# v0_3_2.net
KiCad netlist of a schematic drawn in EAGLE
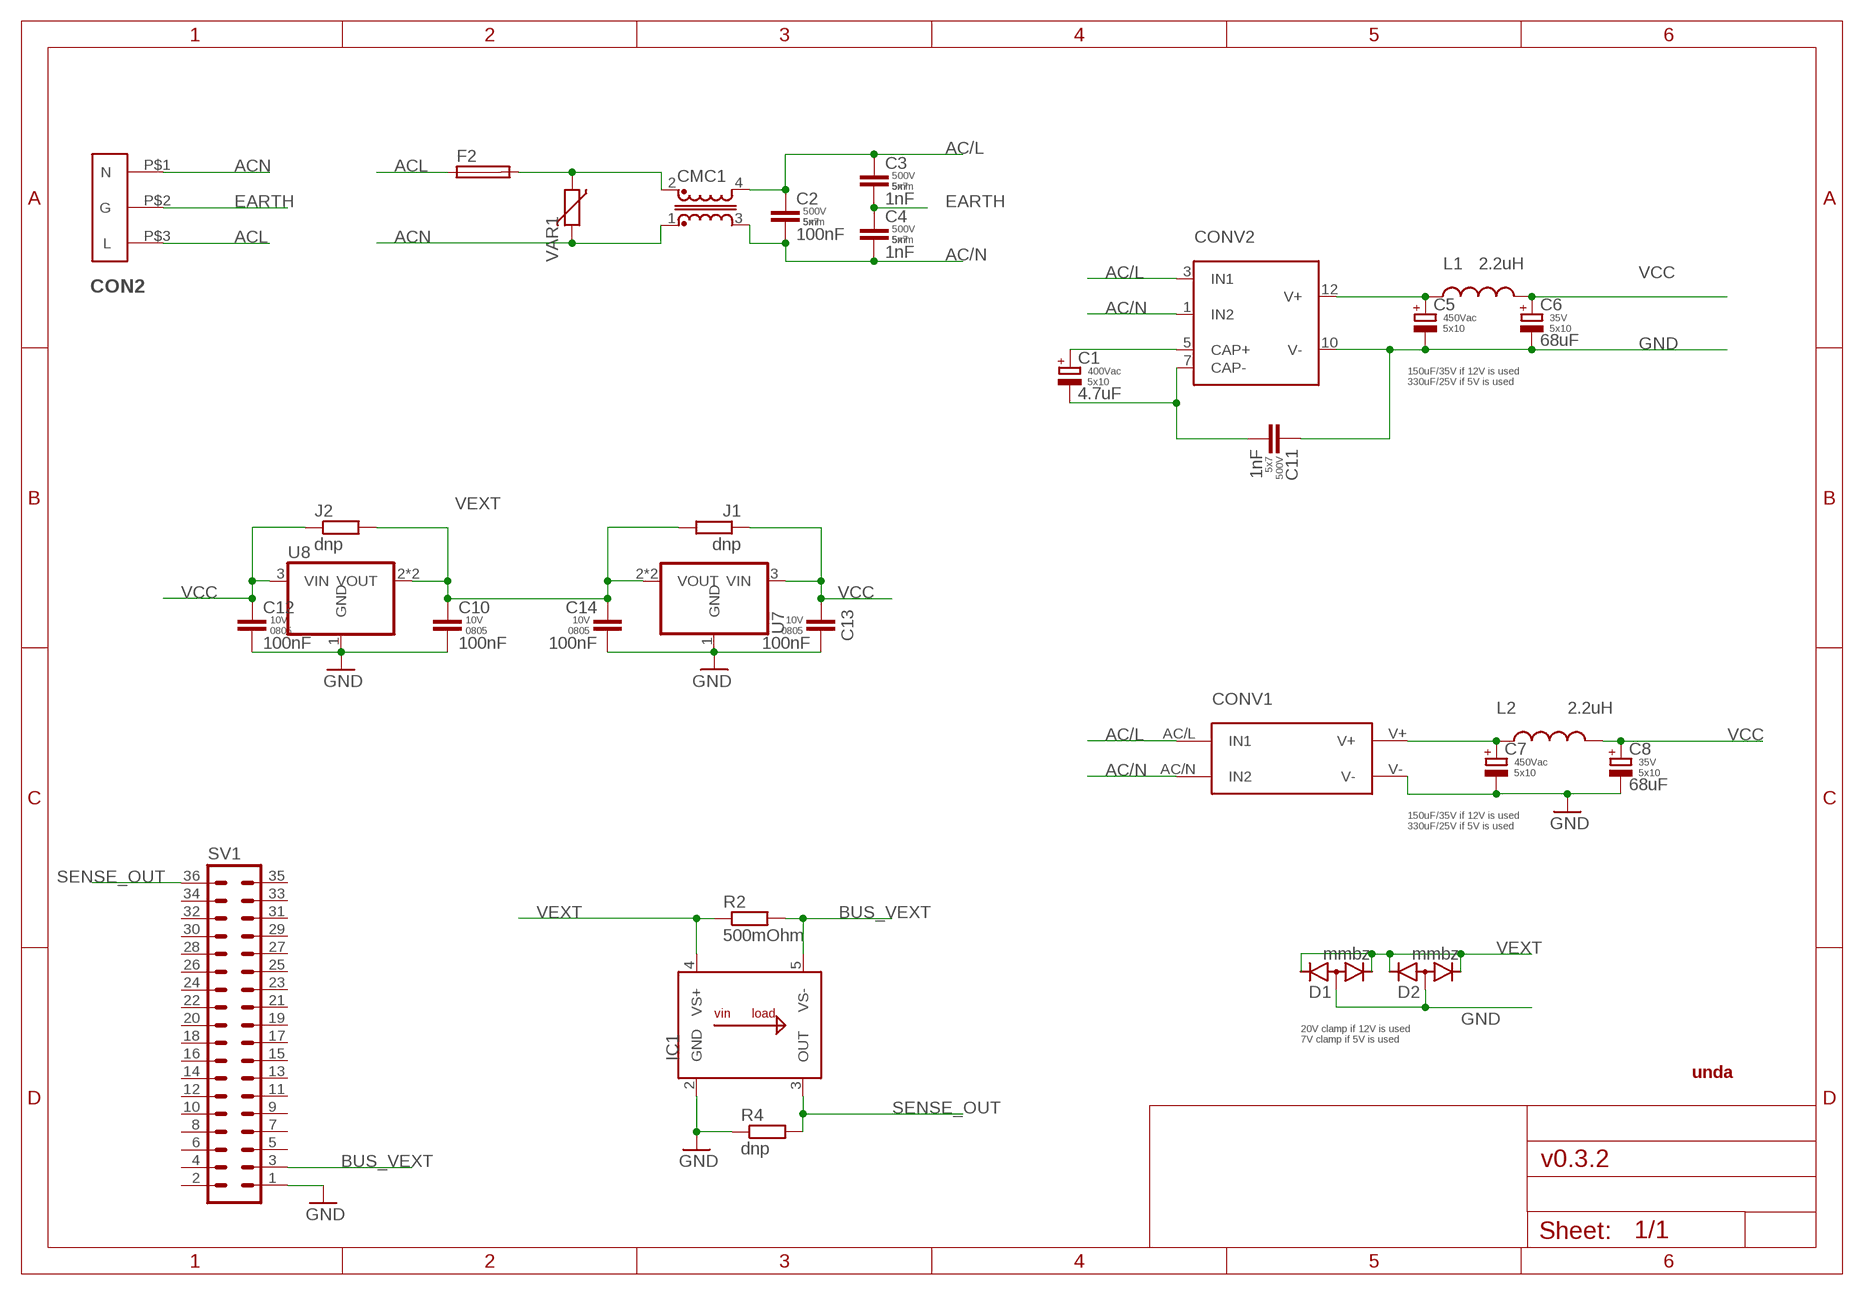
[diagram p0: schematic, sheet 1]

(export (version "E")
  (design (tool "Eeschema 10.0.6"))
  (components
    (comp (ref "C1")
      (value "4.7uF")
      (footprint "eagle-import:CAPPRD508W65D1000H1600B")
      (fields
        (field (name "PACKAGE") "5x10")
        (field (name "RATING") "450Vac")
        (field (name "RATING_1") "400Vac")
      )
      (libsource (lib "eagle-import") (part "CAP-POL-5PX10WX16H"))
    )
    (comp (ref "C2")
      (value "100nF")
      (footprint "eagle-import:C050-025X075")
      (fields
        (field (name "RATING") "500V")
        (field (name "DIMENSIONS") "5mm")
        (field (name "RATING_1") "500V")
      )
      (libsource (lib "eagle-import") (part "CAP-P5W6H8T2.5"))
    )
    (comp (ref "C3")
      (value "1nF")
      (footprint "eagle-import:C050-025X075")
      (fields
        (field (name "RATING") "500V")
        (field (name "DIMENSIONS") "5mm")
        (field (name "RATING_1") "500V")
      )
      (libsource (lib "eagle-import") (part "CAP-P5W6H8T2.5"))
    )
    (comp (ref "C4")
      (value "1nF")
      (footprint "eagle-import:C050-025X075")
      (fields
        (field (name "RATING") "500V")
        (field (name "DIMENSIONS") "5mm")
        (field (name "RATING_1") "500V")
      )
      (libsource (lib "eagle-import") (part "CAP-P5W6H8T2.5"))
    )
    (comp (ref "C5")
      (value "CAP-POL-5PX10WX16H")
      (footprint "eagle-import:CAPPRD508W65D1000H1600B")
      (libsource (lib "eagle-import") (part "CAP-POL-5PX10WX16H"))
    )
    (comp (ref "C6")
      (value "68uF")
      (footprint "eagle-import:CAPPRD508W65D1000H1600B")
      (fields
        (field (name "PACKAGE") "5x10")
        (field (name "RATING") "450Vac")
        (field (name "RATING_1") "35V")
      )
      (libsource (lib "eagle-import") (part "CAP-POL-5PX10WX16H"))
    )
    (comp (ref "C7")
      (value "CAP-POL-5PX10WX16H")
      (footprint "eagle-import:CAPPRD508W65D1000H1600B")
      (libsource (lib "eagle-import") (part "CAP-POL-5PX10WX16H"))
    )
    (comp (ref "C8")
      (value "68uF")
      (footprint "eagle-import:CAPPRD508W65D1000H1600B")
      (fields
        (field (name "PACKAGE") "5x10")
        (field (name "RATING") "450Vac")
        (field (name "RATING_1") "35V")
      )
      (libsource (lib "eagle-import") (part "CAP-POL-5PX10WX16H"))
    )
    (comp (ref "C10")
      (value "100nF")
      (footprint "eagle-import:C0805")
      (fields (field (name "RATING") "10V") (field (name "PACKAGE") "0805"))
      (libsource (lib "eagle-import") (part "CAP-0805"))
    )
    (comp (ref "C11")
      (value "1nF")
      (footprint "eagle-import:C050-025X075")
      (fields (field (name "RATING") "500V") (field (name "PACKAGE") "5x7"))
      (libsource (lib "eagle-import") (part "CAP-P5W6H8T2.5"))
    )
    (comp (ref "C12")
      (value "100nF")
      (footprint "eagle-import:C0805")
      (libsource (lib "eagle-import") (part "CAP-0805"))
    )
    (comp (ref "C13")
      (value "100nF")
      (footprint "eagle-import:C0805")
      (libsource (lib "eagle-import") (part "CAP-0805"))
    )
    (comp (ref "C14")
      (value "100nF")
      (footprint "eagle-import:C0805")
      (fields (field (name "RATING") "10V") (field (name "PACKAGE") "0805"))
      (libsource (lib "eagle-import") (part "CAP-0805"))
    )
    (comp (ref "CMC1")
      (value "DLD-302U-1A")
      (footprint "eagle-import:DLD")
      (libsource (lib "eagle-import") (part "DLD-302U-1A"))
    )
    (comp (ref "CON2")
      (value "4300.0101")
      (footprint "eagle-import:IEC-C6")
      (libsource (lib "eagle-import") (part "4300.0101"))
    )
    (comp (ref "CONV1")
      (value "IRM-03-12V")
      (footprint "eagle-import:IRM-03")
      (libsource (lib "eagle-import") (part "IRM-03-12V"))
    )
    (comp (ref "CONV2")
      (value "AMEOF312SJZ")
      (footprint "eagle-import:AMEOF3-JZ")
      (libsource (lib "eagle-import") (part "AMEOF312SJZ"))
    )
    (comp (ref "D1")
      (value "mmbz")
      (footprint "eagle-import:SOT23")
      (libsource (lib "eagle-import") (part "DIODE-2CA|ACSOT23"))
    )
    (comp (ref "D2")
      (value "mmbz")
      (footprint "eagle-import:SOT23")
      (libsource (lib "eagle-import") (part "DIODE-2CA|ACSOT23"))
    )
    (comp (ref "F2")
      (value "ZH8")
      (footprint "eagle-import:ZH8X2")
      (libsource (lib "eagle-import") (part "ZH8"))
    )
    (comp (ref "IC1")
      (value "ZXCT1021")
      (footprint "eagle-import:SOT95P240X110-5")
      (libsource (lib "eagle-import") (part "ZXCT1021"))
    )
    (comp (ref "J1")
      (value "dnp")
      (footprint "eagle-import:R0805")
      (libsource (lib "eagle-import") (part "R-EU_R0805"))
    )
    (comp (ref "J2")
      (value "dnp")
      (footprint "eagle-import:R0805")
      (libsource (lib "eagle-import") (part "R-EU_R0805"))
    )
    (comp (ref "L1")
      (value "2.2uH")
      (footprint "eagle-import:COIL0608")
      (libsource (lib "eagle-import") (part "COIL0608-0.022"))
    )
    (comp (ref "L2")
      (value "2.2uH")
      (footprint "eagle-import:COIL0608")
      (libsource (lib "eagle-import") (part "COIL0608-0.022"))
    )
    (comp (ref "R2")
      (value "500mOhm")
      (footprint "eagle-import:R0805")
      (libsource (lib "eagle-import") (part "R-EU_R0805"))
    )
    (comp (ref "R4")
      (value "dnp")
      (footprint "eagle-import:R0603")
      (libsource (lib "eagle-import") (part "R-EU_R0603"))
    )
    (comp (ref "SV1")
      (value "MA18-2")
      (footprint "eagle-import:MA18-2")
      (libsource (lib "eagle-import") (part "MA18-2"))
    )
    (comp (ref "U$1")
      (value "UNDA-LOGO-5X")
      (footprint "eagle-import:UNDA_LOGO_2X")
      (libsource (lib "eagle-import") (part "UNDA-LOGO-5X"))
    )
    (comp (ref "U7")
      (value "LD1117S50")
      (footprint "eagle-import:SOT230P700X180-4")
      (libsource (lib "eagle-import") (part "LD1117S50"))
    )
    (comp (ref "U8")
      (value "LD1117S50")
      (footprint "eagle-import:SOT230P700X180-4")
      (libsource (lib "eagle-import") (part "LD1117S50"))
    )
    (comp (ref "VAR1")
      (value "S14K250")
      (footprint "eagle-import:C7.5B4")
      (libsource (lib "eagle-import") (part "S14K250"))
    )
  )
  (nets
    (net (code "1") (name "/ACL") (class "Default")
      (node (ref "CON2") (pin "P$3") (pinfunction "L_P$3") (pintype "bidirectional"))
      (node (ref "F2") (pin "1") (pinfunction "1_1") (pintype "passive"))
      (node (ref "F2") (pin "1A") (pinfunction "1_1A") (pintype "passive"))
    )
    (net (code "2") (name "/ACN") (class "Default")
      (node (ref "CMC1") (pin "1") (pinfunction "1_1") (pintype "passive"))
      (node (ref "CON2") (pin "P$1") (pinfunction "N_P$1") (pintype "bidirectional"))
      (node (ref "VAR1") (pin "1") (pinfunction "1_1") (pintype "passive"))
    )
    (net (code "3") (name "/AC{slash}L") (class "Default")
      (node (ref "C2") (pin "1") (pinfunction "1_1") (pintype "passive"))
      (node (ref "C3") (pin "1") (pinfunction "1_1") (pintype "passive"))
      (node (ref "CMC1") (pin "4") (pinfunction "4_4") (pintype "passive"))
      (node (ref "CONV1") (pin "AC/L") (pinfunction "IN1_AC/L") (pintype "bidirectional"))
      (node (ref "CONV2") (pin "3") (pinfunction "IN1_3") (pintype "bidirectional"))
    )
    (net (code "4") (name "/AC{slash}N") (class "Default")
      (node (ref "C2") (pin "2") (pinfunction "2_2") (pintype "passive"))
      (node (ref "C4") (pin "2") (pinfunction "2_2") (pintype "passive"))
      (node (ref "CMC1") (pin "3") (pinfunction "3_3") (pintype "passive"))
      (node (ref "CONV1") (pin "AC/N") (pinfunction "IN2_AC/N") (pintype "bidirectional"))
      (node (ref "CONV2") (pin "1") (pinfunction "IN2_1") (pintype "bidirectional"))
    )
    (net (code "5") (name "/BUS_VEXT") (class "Default")
      (node (ref "IC1") (pin "5") (pinfunction "VS-_5") (pintype "bidirectional"))
      (node (ref "R2") (pin "2") (pinfunction "2_2") (pintype "passive"))
      (node (ref "SV1") (pin "3") (pinfunction "3_3") (pintype "passive"))
    )
    (net (code "6") (name "/EARTH") (class "Default")
      (node (ref "C3") (pin "2") (pinfunction "2_2") (pintype "passive"))
      (node (ref "C4") (pin "1") (pinfunction "1_1") (pintype "passive"))
      (node (ref "CON2") (pin "P$2") (pinfunction "G_P$2") (pintype "bidirectional"))
    )
    (net (code "7") (name "/SENSE_OUT") (class "Default")
      (node (ref "IC1") (pin "3") (pinfunction "OUT_3") (pintype "bidirectional"))
      (node (ref "R4") (pin "2") (pinfunction "2_2") (pintype "passive"))
      (node (ref "SV1") (pin "36") (pinfunction "36_36") (pintype "passive"))
    )
    (net (code "8") (name "/VCC") (class "Default")
      (node (ref "C12") (pin "1") (pinfunction "1_1") (pintype "passive"))
      (node (ref "C13") (pin "1") (pinfunction "1_1") (pintype "passive"))
      (node (ref "C6") (pin "1") (pinfunction "+_1") (pintype "passive"))
      (node (ref "C8") (pin "1") (pinfunction "+_1") (pintype "passive"))
      (node (ref "J1") (pin "1") (pinfunction "1_1") (pintype "passive"))
      (node (ref "J2") (pin "1") (pinfunction "1_1") (pintype "passive"))
      (node (ref "L1") (pin "P$2") (pinfunction "2_P$2") (pintype "passive"))
      (node (ref "L2") (pin "P$2") (pinfunction "2_P$2") (pintype "passive"))
      (node (ref "U7") (pin "3") (pinfunction "VIN_3") (pintype "input"))
      (node (ref "U8") (pin "3") (pinfunction "VIN_3") (pintype "input"))
    )
    (net (code "9") (name "/VEXT") (class "Default")
      (node (ref "C10") (pin "1") (pinfunction "1_1") (pintype "passive"))
      (node (ref "C14") (pin "1") (pinfunction "1_1") (pintype "passive"))
      (node (ref "D1") (pin "1") (pinfunction "K1_1") (pintype "passive"))
      (node (ref "D1") (pin "2") (pinfunction "K2_2") (pintype "passive"))
      (node (ref "D2") (pin "1") (pinfunction "K1_1") (pintype "passive"))
      (node (ref "D2") (pin "2") (pinfunction "K2_2") (pintype "passive"))
      (node (ref "IC1") (pin "4") (pinfunction "VS+_4") (pintype "bidirectional"))
      (node (ref "J1") (pin "2") (pinfunction "2_2") (pintype "passive"))
      (node (ref "J2") (pin "2") (pinfunction "2_2") (pintype "passive"))
      (node (ref "R2") (pin "1") (pinfunction "1_1") (pintype "passive"))
      (node (ref "U7") (pin "2") (pinfunction "VOUT_2") (pintype "output"))
      (node (ref "U7") (pin "4") (pinfunction "VOUT_4") (pintype "output"))
      (node (ref "U8") (pin "2") (pinfunction "VOUT_2") (pintype "output"))
      (node (ref "U8") (pin "4") (pinfunction "VOUT_4") (pintype "output"))
    )
    (net (code "10") (name "GND") (class "Default")
      (node (ref "C10") (pin "2") (pinfunction "2_2") (pintype "passive"))
      (node (ref "C11") (pin "1") (pinfunction "1_1") (pintype "passive"))
      (node (ref "C12") (pin "2") (pinfunction "2_2") (pintype "passive"))
      (node (ref "C13") (pin "2") (pinfunction "2_2") (pintype "passive"))
      (node (ref "C14") (pin "2") (pinfunction "2_2") (pintype "passive"))
      (node (ref "C5") (pin "2") (pinfunction "-_2") (pintype "passive"))
      (node (ref "C6") (pin "2") (pinfunction "-_2") (pintype "passive"))
      (node (ref "C7") (pin "2") (pinfunction "-_2") (pintype "passive"))
      (node (ref "C8") (pin "2") (pinfunction "-_2") (pintype "passive"))
      (node (ref "CONV1") (pin "V-") (pinfunction "V-_V-") (pintype "bidirectional"))
      (node (ref "CONV2") (pin "10") (pinfunction "V-_10") (pintype "bidirectional"))
      (node (ref "D1") (pin "3") (pinfunction "A_3") (pintype "passive"))
      (node (ref "D2") (pin "3") (pinfunction "A_3") (pintype "passive"))
      (node (ref "IC1") (pin "2") (pinfunction "GND_2") (pintype "bidirectional"))
      (node (ref "R4") (pin "1") (pinfunction "1_1") (pintype "passive"))
      (node (ref "SV1") (pin "1") (pinfunction "1_1") (pintype "passive"))
      (node (ref "U7") (pin "1") (pinfunction "GND_1") (pintype "power_in"))
      (node (ref "U8") (pin "1") (pinfunction "GND_1") (pintype "power_in"))
    )
    (net (code "11") (name "Net-(C1-+)") (class "Default")
      (node (ref "C1") (pin "1") (pinfunction "+_1") (pintype "passive"))
      (node (ref "CONV2") (pin "5") (pinfunction "CAP+_5") (pintype "bidirectional"))
    )
    (net (code "12") (name "Net-(C1--)") (class "Default")
      (node (ref "C1") (pin "2") (pinfunction "-_2") (pintype "passive"))
      (node (ref "C11") (pin "2") (pinfunction "2_2") (pintype "passive"))
      (node (ref "CONV2") (pin "7") (pinfunction "CAP-_7") (pintype "bidirectional"))
    )
    (net (code "13") (name "Net-(C5-+)") (class "Default")
      (node (ref "C5") (pin "1") (pinfunction "+_1") (pintype "passive"))
      (node (ref "CONV2") (pin "12") (pinfunction "V+_12") (pintype "bidirectional"))
      (node (ref "L1") (pin "P$1") (pinfunction "1_P$1") (pintype "passive"))
    )
    (net (code "14") (name "Net-(C7-+)") (class "Default")
      (node (ref "C7") (pin "1") (pinfunction "+_1") (pintype "passive"))
      (node (ref "CONV1") (pin "V+") (pinfunction "V+_V+") (pintype "bidirectional"))
      (node (ref "L2") (pin "P$1") (pinfunction "1_P$1") (pintype "passive"))
    )
    (net (code "15") (name "Net-(CMC1-Pad2)") (class "Default")
      (node (ref "CMC1") (pin "2") (pinfunction "2_2") (pintype "passive"))
      (node (ref "F2") (pin "2") (pinfunction "2_2") (pintype "passive"))
      (node (ref "F2") (pin "2A") (pinfunction "2_2A") (pintype "passive"))
      (node (ref "VAR1") (pin "2") (pinfunction "2_2") (pintype "passive"))
    )
    (net (code "16") (name "unconnected-(SV1-Pad2)") (class "Default")
      (node (ref "SV1") (pin "2") (pinfunction "2_2") (pintype "passive"))
    )
    (net (code "17") (name "unconnected-(SV1-Pad4)") (class "Default")
      (node (ref "SV1") (pin "4") (pinfunction "4_4") (pintype "passive"))
    )
    (net (code "18") (name "unconnected-(SV1-Pad5)") (class "Default")
      (node (ref "SV1") (pin "5") (pinfunction "5_5") (pintype "passive"))
    )
    (net (code "19") (name "unconnected-(SV1-Pad6)") (class "Default")
      (node (ref "SV1") (pin "6") (pinfunction "6_6") (pintype "passive"))
    )
    (net (code "20") (name "unconnected-(SV1-Pad7)") (class "Default")
      (node (ref "SV1") (pin "7") (pinfunction "7_7") (pintype "passive"))
    )
    (net (code "21") (name "unconnected-(SV1-Pad8)") (class "Default")
      (node (ref "SV1") (pin "8") (pinfunction "8_8") (pintype "passive"))
    )
    (net (code "22") (name "unconnected-(SV1-Pad9)") (class "Default")
      (node (ref "SV1") (pin "9") (pinfunction "9_9") (pintype "passive"))
    )
    (net (code "23") (name "unconnected-(SV1-Pad10)") (class "Default")
      (node (ref "SV1") (pin "10") (pinfunction "10_10") (pintype "passive"))
    )
    (net (code "24") (name "unconnected-(SV1-Pad11)") (class "Default")
      (node (ref "SV1") (pin "11") (pinfunction "11_11") (pintype "passive"))
    )
    (net (code "25") (name "unconnected-(SV1-Pad12)") (class "Default")
      (node (ref "SV1") (pin "12") (pinfunction "12_12") (pintype "passive"))
    )
    (net (code "26") (name "unconnected-(SV1-Pad13)") (class "Default")
      (node (ref "SV1") (pin "13") (pinfunction "13_13") (pintype "passive"))
    )
    (net (code "27") (name "unconnected-(SV1-Pad14)") (class "Default")
      (node (ref "SV1") (pin "14") (pinfunction "14_14") (pintype "passive"))
    )
    (net (code "28") (name "unconnected-(SV1-Pad15)") (class "Default")
      (node (ref "SV1") (pin "15") (pinfunction "15_15") (pintype "passive"))
    )
    (net (code "29") (name "unconnected-(SV1-Pad16)") (class "Default")
      (node (ref "SV1") (pin "16") (pinfunction "16_16") (pintype "passive"))
    )
    (net (code "30") (name "unconnected-(SV1-Pad17)") (class "Default")
      (node (ref "SV1") (pin "17") (pinfunction "17_17") (pintype "passive"))
    )
    (net (code "31") (name "unconnected-(SV1-Pad18)") (class "Default")
      (node (ref "SV1") (pin "18") (pinfunction "18_18") (pintype "passive"))
    )
    (net (code "32") (name "unconnected-(SV1-Pad19)") (class "Default")
      (node (ref "SV1") (pin "19") (pinfunction "19_19") (pintype "passive"))
    )
    (net (code "33") (name "unconnected-(SV1-Pad20)") (class "Default")
      (node (ref "SV1") (pin "20") (pinfunction "20_20") (pintype "passive"))
    )
    (net (code "34") (name "unconnected-(SV1-Pad21)") (class "Default")
      (node (ref "SV1") (pin "21") (pinfunction "21_21") (pintype "passive"))
    )
    (net (code "35") (name "unconnected-(SV1-Pad22)") (class "Default")
      (node (ref "SV1") (pin "22") (pinfunction "22_22") (pintype "passive"))
    )
    (net (code "36") (name "unconnected-(SV1-Pad23)") (class "Default")
      (node (ref "SV1") (pin "23") (pinfunction "23_23") (pintype "passive"))
    )
    (net (code "37") (name "unconnected-(SV1-Pad24)") (class "Default")
      (node (ref "SV1") (pin "24") (pinfunction "24_24") (pintype "passive"))
    )
    (net (code "38") (name "unconnected-(SV1-Pad25)") (class "Default")
      (node (ref "SV1") (pin "25") (pinfunction "25_25") (pintype "passive"))
    )
    (net (code "39") (name "unconnected-(SV1-Pad26)") (class "Default")
      (node (ref "SV1") (pin "26") (pinfunction "26_26") (pintype "passive"))
    )
    (net (code "40") (name "unconnected-(SV1-Pad27)") (class "Default")
      (node (ref "SV1") (pin "27") (pinfunction "27_27") (pintype "passive"))
    )
    (net (code "41") (name "unconnected-(SV1-Pad28)") (class "Default")
      (node (ref "SV1") (pin "28") (pinfunction "28_28") (pintype "passive"))
    )
    (net (code "42") (name "unconnected-(SV1-Pad29)") (class "Default")
      (node (ref "SV1") (pin "29") (pinfunction "29_29") (pintype "passive"))
    )
    (net (code "43") (name "unconnected-(SV1-Pad30)") (class "Default")
      (node (ref "SV1") (pin "30") (pinfunction "30_30") (pintype "passive"))
    )
    (net (code "44") (name "unconnected-(SV1-Pad31)") (class "Default")
      (node (ref "SV1") (pin "31") (pinfunction "31_31") (pintype "passive"))
    )
    (net (code "45") (name "unconnected-(SV1-Pad32)") (class "Default")
      (node (ref "SV1") (pin "32") (pinfunction "32_32") (pintype "passive"))
    )
    (net (code "46") (name "unconnected-(SV1-Pad33)") (class "Default")
      (node (ref "SV1") (pin "33") (pinfunction "33_33") (pintype "passive"))
    )
    (net (code "47") (name "unconnected-(SV1-Pad34)") (class "Default")
      (node (ref "SV1") (pin "34") (pinfunction "34_34") (pintype "passive"))
    )
    (net (code "48") (name "unconnected-(SV1-Pad35)") (class "Default")
      (node (ref "SV1") (pin "35") (pinfunction "35_35") (pintype "passive"))
    )
  )
)
